# Processor.net
KiCad netlist of a schematic drawn in Altium Designer
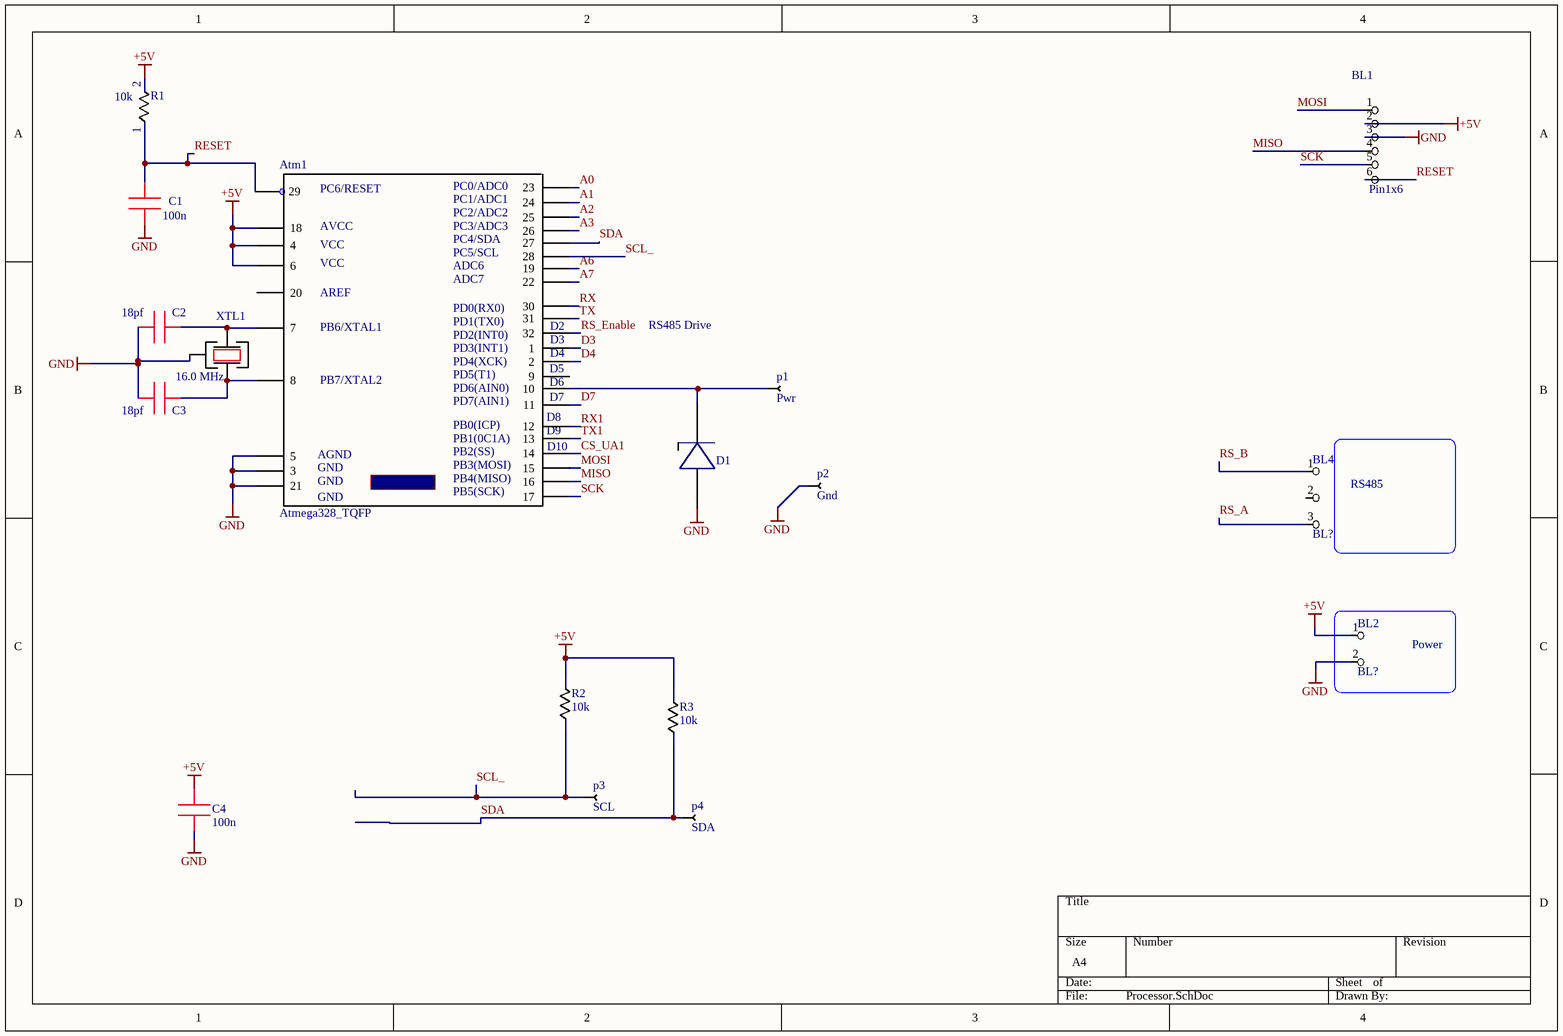
[diagram p0: Processor.SchDoc]

(export (version "E")
  (design (tool "Eeschema 10.0.6"))
  (components
    (comp (ref "Atm1")
      (value "Atmega328_TQFP")
      (footprint "TQFP")
      (libsource (lib "kontr") (part "Atmega328_TQFP"))
    )
    (comp (ref "BL1")
      (value "Pin1x6")
      (footprint "Pin_6 1,27")
      (description "PLL-6")
      (libsource (lib "kontr") (part "Pin1x6"))
    )
    (comp (ref "BL2") (value "BL?") (footprint "2.54 2pin") (libsource (lib "kontr") (part "2.54 2pin")))
    (comp (ref "BL4") (value "BL?") (footprint "2.54 3pin") (libsource (lib "kontr") (part "2.54 3pin")))
    (comp (ref "C1")
      (value "100n")
      (footprint "0402")
      (description "C1005X7R1H104K050BB")
      (libsource (lib "kontr") (part "Capasitor 0805"))
    )
    (comp (ref "C2")
      (value "18pf")
      (footprint "0402")
      (description "CC0402JRNPO9BN180")
      (libsource (lib "kontr") (part "Capasitor 0805"))
    )
    (comp (ref "C3")
      (value "18pf")
      (footprint "0402")
      (description "CC0402JRNPO9BN180")
      (libsource (lib "kontr") (part "Capasitor 0805"))
    )
    (comp (ref "C4")
      (value "100n")
      (footprint "0402")
      (description "C1005X7R1H104K050BB")
      (libsource (lib "kontr") (part "0805 Cap"))
    )
    (comp (ref "D1")
      (value "zener")
      (footprint "Sot23-3")
      (description "BZX84C5V6LT1G")
      (libsource (lib "kontr") (part "BZX84"))
    )
    (comp (ref "p1")
      (value "Pwr")
      (footprint "Wire Pin 0.5")
      (description "pin")
      (libsource (lib "kontr") (part "PIN_Wire"))
    )
    (comp (ref "p2")
      (value "Gnd")
      (footprint "Wire Pin 0.5")
      (description "pin")
      (libsource (lib "kontr") (part "PIN_Wire"))
    )
    (comp (ref "p3")
      (value "SCL")
      (footprint "Wire Pin 0.5")
      (description "pin")
      (libsource (lib "kontr") (part "PIN_Wire"))
    )
    (comp (ref "p4")
      (value "SDA")
      (footprint "Wire Pin 0.5")
      (description "pin")
      (libsource (lib "kontr") (part "PIN_Wire"))
    )
    (comp (ref "R1")
      (value "10k")
      (footprint "0402")
      (description "RC0402FR-0710KL")
      (libsource (lib "") (part "Resistor 0805_1"))
    )
    (comp (ref "R2")
      (value "10k")
      (footprint "0402")
      (description "RC0402FR-0710KL")
      (libsource (lib "kontr") (part "Resistor 0805"))
    )
    (comp (ref "R3")
      (value "10k")
      (footprint "0402")
      (description "RC0402FR-0710KL")
      (libsource (lib "kontr") (part "Resistor 0805"))
    )
    (comp (ref "XTL1")
      (value "16.0 MHz")
      (footprint "KX-7 XTAL")
      (description "KX-7T 16.0 MHz 50/100/100")
      (libsource (lib "kontr") (part "KX-7"))
    )
  )
  (nets
    (net (code "1") (name "+5V") (class "Default")
      (node (ref "Atm1") (pin "18") (pinfunction "18_18") (pintype "passive"))
      (node (ref "Atm1") (pin "4") (pinfunction "4_4") (pintype "passive"))
      (node (ref "Atm1") (pin "6") (pinfunction "6_6") (pintype "passive"))
      (node (ref "BL1") (pin "2") (pinfunction "2_2") (pintype "passive"))
      (node (ref "BL2") (pin "1") (pinfunction "1_1") (pintype "passive"))
      (node (ref "C4") (pin "2") (pinfunction "2_2") (pintype "passive"))
      (node (ref "R1") (pin "2") (pintype "passive"))
      (node (ref "R2") (pin "2") (pintype "passive"))
      (node (ref "R3") (pin "2") (pintype "passive"))
    )
    (net (code "2") (name "/A0") (class "Default")
      (node (ref "Atm1") (pin "23") (pinfunction "23_23") (pintype "passive"))
    )
    (net (code "3") (name "/A1") (class "Default")
      (node (ref "Atm1") (pin "24") (pinfunction "24_24") (pintype "passive"))
    )
    (net (code "4") (name "/A2") (class "Default")
      (node (ref "Atm1") (pin "25") (pinfunction "25_25") (pintype "passive"))
    )
    (net (code "5") (name "/A3") (class "Default")
      (node (ref "Atm1") (pin "26") (pinfunction "26_26") (pintype "passive"))
    )
    (net (code "6") (name "/A6") (class "Default")
      (node (ref "Atm1") (pin "19") (pinfunction "19_19") (pintype "passive"))
    )
    (net (code "7") (name "/A7") (class "Default")
      (node (ref "Atm1") (pin "22") (pinfunction "22_22") (pintype "passive"))
    )
    (net (code "8") (name "/CS_UA1") (class "Default")
      (node (ref "Atm1") (pin "14") (pinfunction "14_14") (pintype "passive"))
    )
    (net (code "9") (name "/D3") (class "Default")
      (node (ref "Atm1") (pin "1") (pinfunction "1_1") (pintype "passive"))
    )
    (net (code "10") (name "/D4") (class "Default")
      (node (ref "Atm1") (pin "2") (pinfunction "2_2") (pintype "passive"))
    )
    (net (code "11") (name "/D7") (class "Default")
      (node (ref "Atm1") (pin "11") (pinfunction "11_11") (pintype "passive"))
    )
    (net (code "12") (name "/MISO") (class "Default")
      (node (ref "Atm1") (pin "16") (pinfunction "16_16") (pintype "passive"))
      (node (ref "BL1") (pin "4") (pinfunction "4_4") (pintype "passive"))
    )
    (net (code "13") (name "/MOSI") (class "Default")
      (node (ref "Atm1") (pin "15") (pinfunction "15_15") (pintype "passive"))
      (node (ref "BL1") (pin "1") (pinfunction "1_1") (pintype "passive"))
    )
    (net (code "14") (name "/RESET") (class "Default")
      (node (ref "Atm1") (pin "29") (pinfunction "29_29") (pintype "passive"))
      (node (ref "BL1") (pin "6") (pinfunction "6_6") (pintype "passive"))
      (node (ref "C1") (pin "2") (pinfunction "2_2") (pintype "passive"))
      (node (ref "R1") (pin "1") (pintype "passive"))
    )
    (net (code "15") (name "/RS_A") (class "Default")
      (node (ref "BL4") (pin "3") (pinfunction "3_3") (pintype "passive"))
    )
    (net (code "16") (name "/RS_B") (class "Default")
      (node (ref "BL4") (pin "1") (pinfunction "1_1") (pintype "passive"))
    )
    (net (code "17") (name "/RS_Enable") (class "Default")
      (node (ref "Atm1") (pin "32") (pinfunction "32_32") (pintype "passive"))
    )
    (net (code "18") (name "/RX") (class "Default")
      (node (ref "Atm1") (pin "30") (pinfunction "30_30") (pintype "passive"))
    )
    (net (code "19") (name "/RX1") (class "Default")
      (node (ref "Atm1") (pin "12") (pinfunction "12_12") (pintype "passive"))
    )
    (net (code "20") (name "/SCK") (class "Default")
      (node (ref "Atm1") (pin "17") (pinfunction "17_17") (pintype "passive"))
      (node (ref "BL1") (pin "5") (pinfunction "5_5") (pintype "passive"))
    )
    (net (code "21") (name "/SCL_") (class "Default")
      (node (ref "Atm1") (pin "28") (pinfunction "28_28") (pintype "passive"))
      (node (ref "R2") (pin "1") (pintype "passive"))
      (node (ref "p3") (pin "1") (pinfunction "1_1") (pintype "passive"))
    )
    (net (code "22") (name "/SDA") (class "Default")
      (node (ref "Atm1") (pin "27") (pinfunction "27_27") (pintype "passive"))
      (node (ref "R3") (pin "1") (pintype "passive"))
      (node (ref "p4") (pin "1") (pinfunction "1_1") (pintype "passive"))
    )
    (net (code "23") (name "/TX") (class "Default")
      (node (ref "Atm1") (pin "31") (pinfunction "31_31") (pintype "passive"))
    )
    (net (code "24") (name "/TX1") (class "Default")
      (node (ref "Atm1") (pin "13") (pinfunction "13_13") (pintype "passive"))
    )
    (net (code "25") (name "GND") (class "Default")
      (node (ref "Atm1") (pin "21") (pinfunction "21_21") (pintype "passive"))
      (node (ref "Atm1") (pin "3") (pinfunction "3_3") (pintype "passive"))
      (node (ref "Atm1") (pin "5") (pinfunction "5_5") (pintype "passive"))
      (node (ref "BL1") (pin "3") (pinfunction "3_3") (pintype "passive"))
      (node (ref "BL2") (pin "2") (pinfunction "2_2") (pintype "passive"))
      (node (ref "C1") (pin "1") (pinfunction "1_1") (pintype "passive"))
      (node (ref "C2") (pin "1") (pinfunction "1_1") (pintype "passive"))
      (node (ref "C3") (pin "1") (pinfunction "1_1") (pintype "passive"))
      (node (ref "C4") (pin "1") (pinfunction "1_1") (pintype "passive"))
      (node (ref "D1") (pin "1") (pinfunction "1_1") (pintype "passive"))
      (node (ref "XTL1") (pin "2") (pinfunction "2_2") (pintype "passive"))
      (node (ref "p2") (pin "1") (pinfunction "1_1") (pintype "passive"))
    )
    (net (code "26") (name "Net-(Atm1-Pad7)") (class "Default")
      (node (ref "Atm1") (pin "7") (pinfunction "7_7") (pintype "passive"))
      (node (ref "C2") (pin "2") (pinfunction "2_2") (pintype "passive"))
      (node (ref "XTL1") (pin "1") (pinfunction "5_1") (pintype "passive"))
    )
    (net (code "27") (name "Net-(Atm1-Pad8)") (class "Default")
      (node (ref "Atm1") (pin "8") (pinfunction "8_8") (pintype "passive"))
      (node (ref "C3") (pin "2") (pinfunction "2_2") (pintype "passive"))
      (node (ref "XTL1") (pin "3") (pinfunction "5_3") (pintype "passive"))
    )
    (net (code "28") (name "Net-(Atm1-Pad10)") (class "Default")
      (node (ref "Atm1") (pin "10") (pinfunction "10_10") (pintype "passive"))
      (node (ref "D1") (pin "3") (pinfunction "3_3") (pintype "passive"))
      (node (ref "p1") (pin "1") (pinfunction "1_1") (pintype "passive"))
    )
    (net (code "29") (name "unconnected-(Atm1-Pad9)") (class "Default")
      (node (ref "Atm1") (pin "9") (pinfunction "9_9") (pintype "passive"))
    )
    (net (code "30") (name "unconnected-(Atm1-Pad20)") (class "Default")
      (node (ref "Atm1") (pin "20") (pinfunction "20_20") (pintype "passive"))
    )
    (net (code "31") (name "unconnected-(BL4-Pad2)") (class "Default")
      (node (ref "BL4") (pin "2") (pinfunction "2_2") (pintype "passive"))
    )
  )
)
